# SOC_PWR.net
KiCad netlist of a schematic drawn in Altium Designer
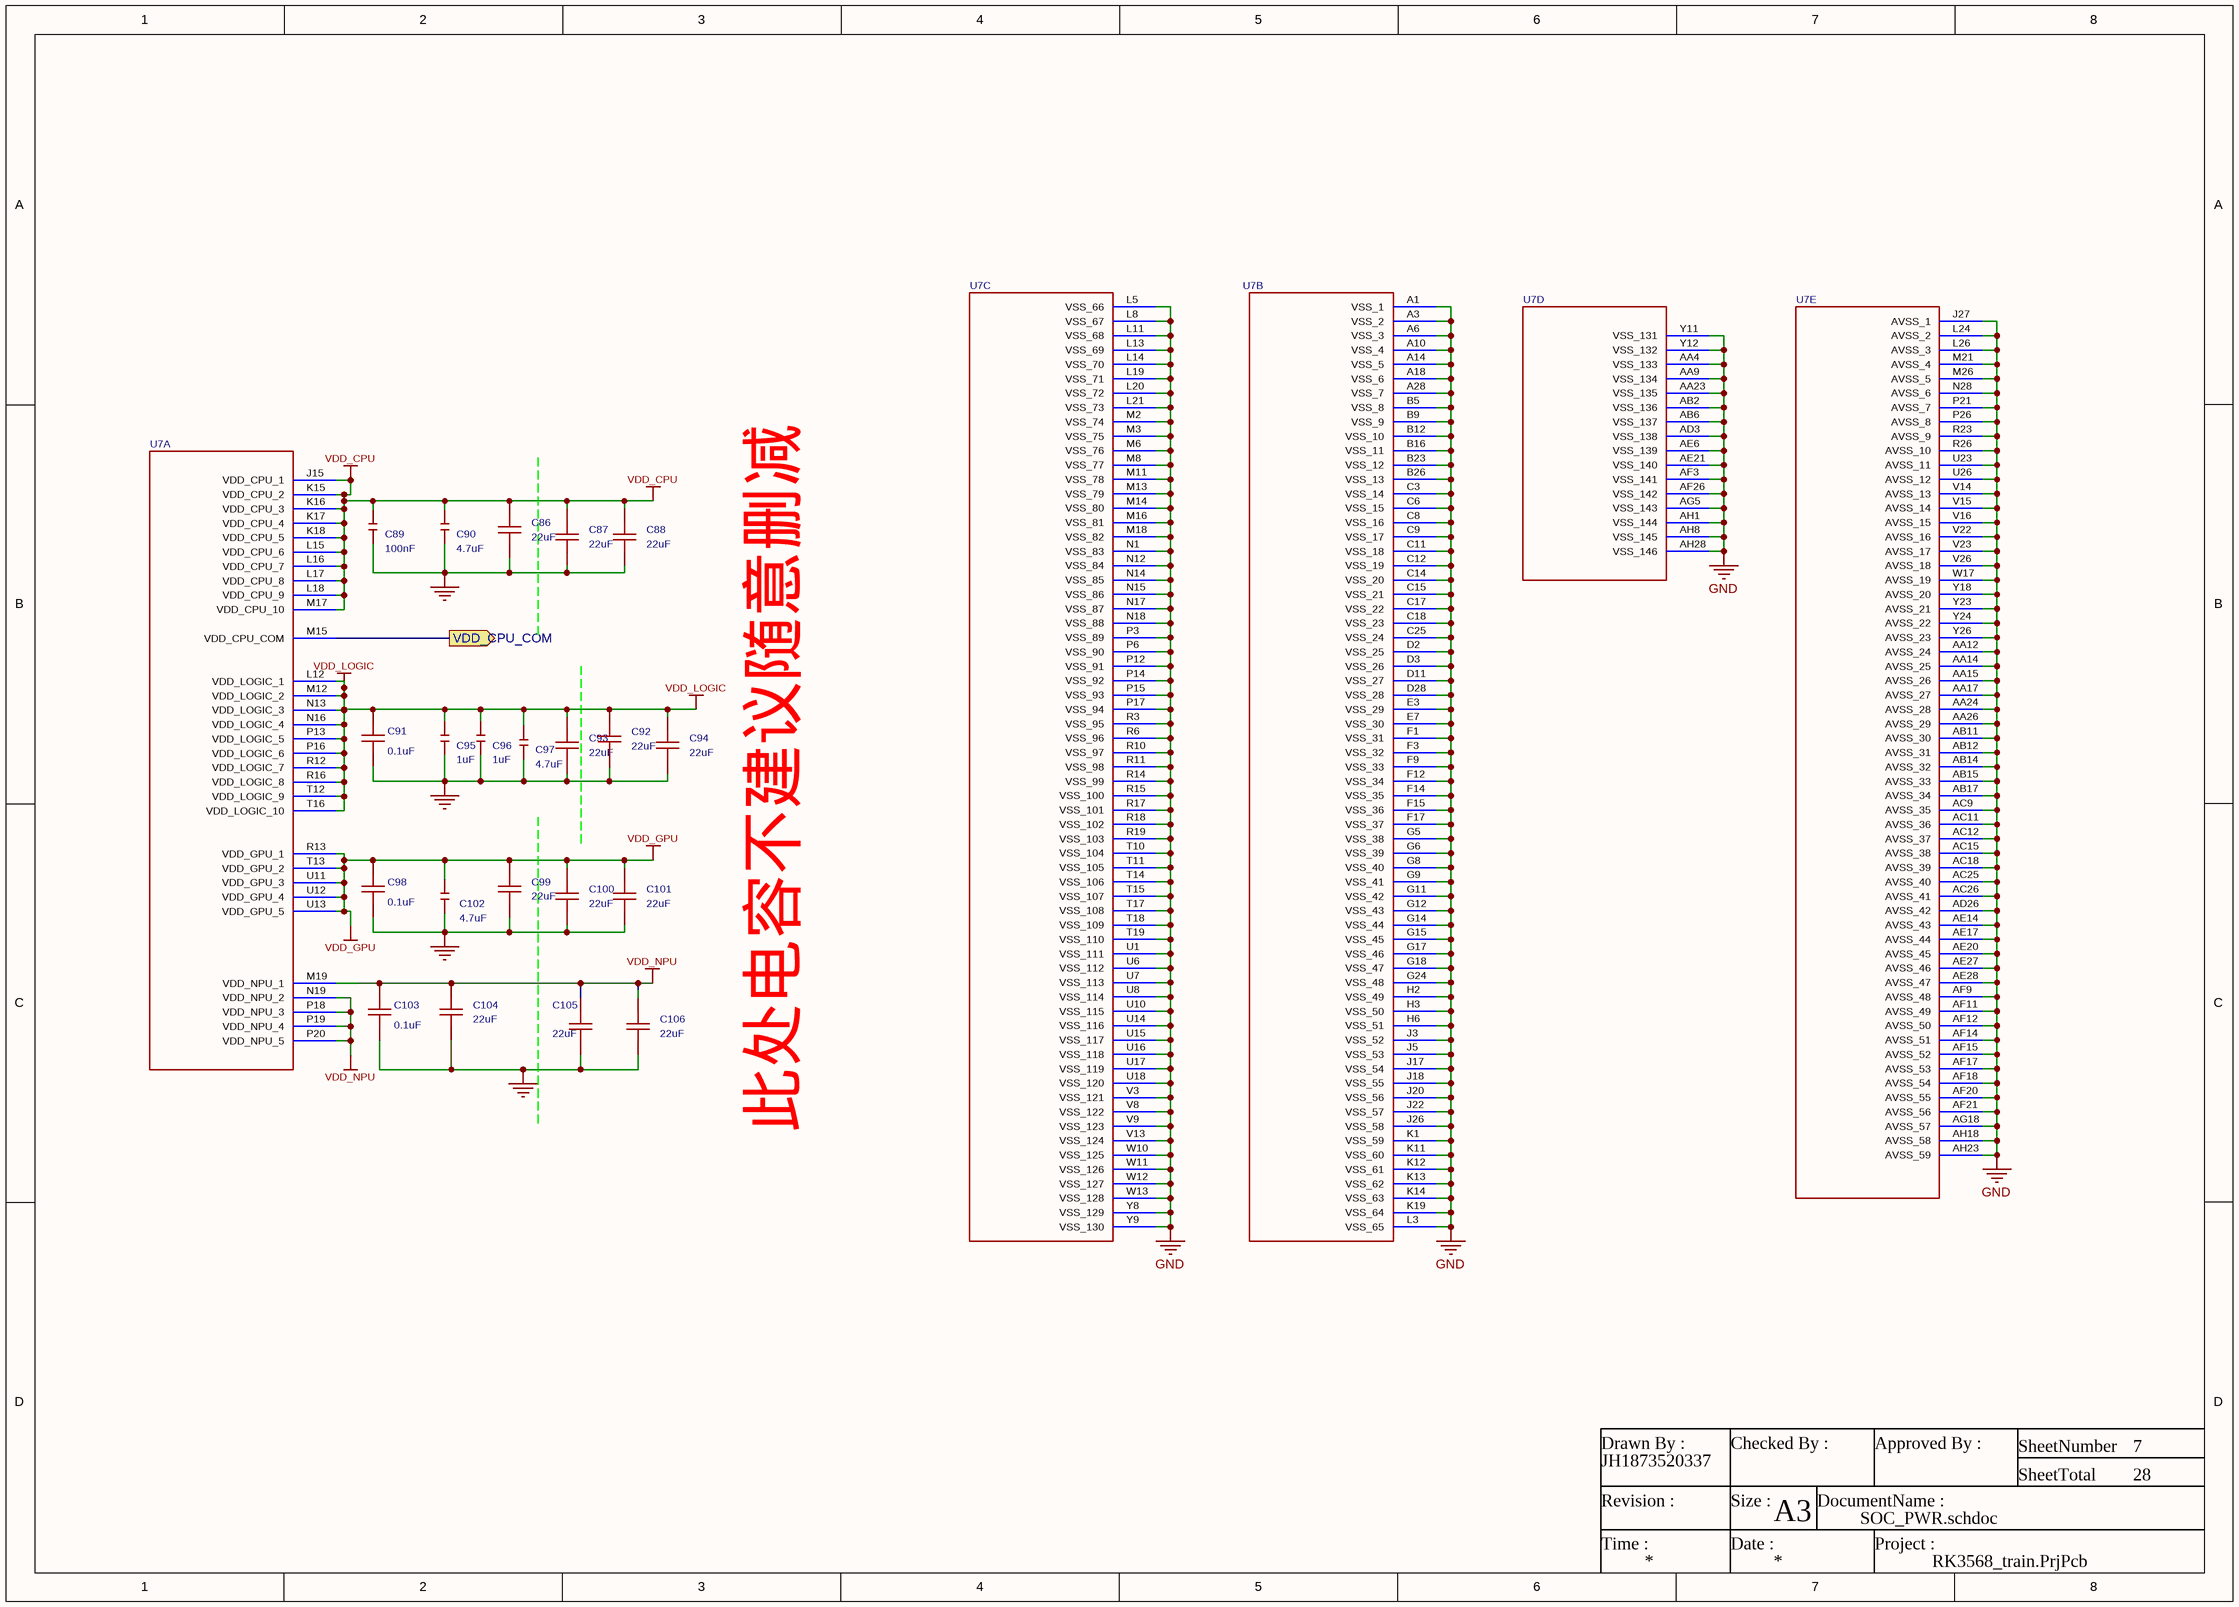
[diagram p0: SOC_PWR.schdoc]

(export (version "E")
  (design (tool "Eeschema 10.0.6"))
  (components
    (comp (ref "C86")
      (value "22uF")
      (footprint "C0603")
      (libsource (lib "altium-import") (part "root_1_CAP_0603_"))
    )
    (comp (ref "C87")
      (value "22uF")
      (footprint "C0603")
      (libsource (lib "altium-import") (part "root_1_CAP_0603_"))
    )
    (comp (ref "C88")
      (value "22uF")
      (footprint "C0603")
      (libsource (lib "altium-import") (part "root_1_CAP_0603_"))
    )
    (comp (ref "C89")
      (value "100nF")
      (footprint "MYC0402")
      (description "C0402电容")
      (libsource (lib "altium-import") (part "root_1_MYC0402_"))
    )
    (comp (ref "C90")
      (value "4.7uF")
      (footprint "MYC0402")
      (description "C0402电容")
      (libsource (lib "altium-import") (part "root_1_MYC0402_"))
    )
    (comp (ref "C91")
      (value "0.1uF")
      (footprint "C0201")
      (description "容值:4.7uF;精度:±20%;额定电压:6.3V;温度系数:X5R;")
      (fields
        (field (name "MANUFACTURER") "muRata(村田)")
        (field (name "MANUFACTURERPART") "GRM035R60J475ME15D")
      )
      (libsource (lib "altium-import") (part "root_0_GRM035R60J475ME15D_"))
    )
    (comp (ref "C92")
      (value "22uF")
      (footprint "C0603")
      (libsource (lib "altium-import") (part "root_1_CAP_0603_"))
    )
    (comp (ref "C93")
      (value "22uF")
      (footprint "C0603")
      (libsource (lib "altium-import") (part "root_1_CAP_0603_"))
    )
    (comp (ref "C94")
      (value "22uF")
      (footprint "C0603")
      (libsource (lib "altium-import") (part "root_1_CAP_0603_"))
    )
    (comp (ref "C95")
      (value "1uF")
      (footprint "MYC0402")
      (description "C0402电容")
      (libsource (lib "altium-import") (part "root_1_MYC0402_"))
    )
    (comp (ref "C96")
      (value "1uF")
      (footprint "MYC0402")
      (description "C0402电容")
      (libsource (lib "altium-import") (part "root_1_MYC0402_"))
    )
    (comp (ref "C97")
      (value "4.7uF")
      (footprint "MYC0402")
      (description "C0402电容")
      (libsource (lib "altium-import") (part "root_1_MYC0402_"))
    )
    (comp (ref "C98")
      (value "0.1uF")
      (footprint "C0201")
      (description "容值:4.7uF;精度:±20%;额定电压:6.3V;温度系数:X5R;")
      (fields
        (field (name "MANUFACTURER") "muRata(村田)")
        (field (name "MANUFACTURERPART") "GRM035R60J475ME15D")
      )
      (libsource (lib "altium-import") (part "root_0_GRM035R60J475ME15D_"))
    )
    (comp (ref "C99")
      (value "22uF")
      (footprint "C0603")
      (libsource (lib "altium-import") (part "root_1_CAP_0603_"))
    )
    (comp (ref "C100")
      (value "22uF")
      (footprint "C0603")
      (libsource (lib "altium-import") (part "root_1_CAP_0603_"))
    )
    (comp (ref "C101")
      (value "22uF")
      (footprint "C0603")
      (libsource (lib "altium-import") (part "root_1_CAP_0603_"))
    )
    (comp (ref "C102")
      (value "4.7uF")
      (footprint "MYC0402")
      (description "C0402电容")
      (libsource (lib "altium-import") (part "root_1_MYC0402_"))
    )
    (comp (ref "C103")
      (value "0.1uF")
      (footprint "C0201")
      (description "容值:4.7uF;精度:±20%;额定电压:6.3V;温度系数:X5R;")
      (fields
        (field (name "MANUFACTURER") "muRata(村田)")
        (field (name "MANUFACTURERPART") "GRM035R60J475ME15D")
      )
      (libsource (lib "altium-import") (part "root_0_GRM035R60J475ME15D_"))
    )
    (comp (ref "C104")
      (value "22uF")
      (footprint "C0603")
      (libsource (lib "altium-import") (part "root_1_CAP_0603_"))
    )
    (comp (ref "C105")
      (value "22uF")
      (footprint "C0603")
      (libsource (lib "altium-import") (part "root_1_CAP_0603_"))
    )
    (comp (ref "C106")
      (value "22uF")
      (footprint "C0603")
      (libsource (lib "altium-import") (part "root_1_CAP_0603_"))
    )
    (comp (ref "U7")
      (value "RK3568")
      (footprint "BGA-636_L19.0-W19.0-P0.65-BL")
      (libsource (lib "altium-import") (part "root_0_RK3568_"))
    )
  )
  (nets
    (net (code "1") (name "/VDD_CPU_COM") (class "Default")
      (node (ref "U7") (pin "M15") (pinfunction "VDD_CPU_COM_M15") (pintype "passive"))
    )
    (net (code "2") (name "GND") (class "Default")
      (node (ref "C100") (pin "1") (pinfunction "1_1") (pintype "passive"))
      (node (ref "C101") (pin "1") (pinfunction "1_1") (pintype "passive"))
      (node (ref "C102") (pin "1") (pinfunction "1_1") (pintype "passive"))
      (node (ref "C103") (pin "1") (pinfunction "1_1") (pintype "passive"))
      (node (ref "C104") (pin "1") (pinfunction "1_1") (pintype "passive"))
      (node (ref "C105") (pin "1") (pinfunction "1_1") (pintype "passive"))
      (node (ref "C106") (pin "1") (pinfunction "1_1") (pintype "passive"))
      (node (ref "C86") (pin "1") (pinfunction "1_1") (pintype "passive"))
      (node (ref "C87") (pin "1") (pinfunction "1_1") (pintype "passive"))
      (node (ref "C88") (pin "1") (pinfunction "1_1") (pintype "passive"))
      (node (ref "C89") (pin "1") (pinfunction "1_1") (pintype "passive"))
      (node (ref "C90") (pin "1") (pinfunction "1_1") (pintype "passive"))
      (node (ref "C91") (pin "1") (pinfunction "1_1") (pintype "passive"))
      (node (ref "C92") (pin "1") (pinfunction "1_1") (pintype "passive"))
      (node (ref "C93") (pin "1") (pinfunction "1_1") (pintype "passive"))
      (node (ref "C94") (pin "1") (pinfunction "1_1") (pintype "passive"))
      (node (ref "C95") (pin "1") (pinfunction "1_1") (pintype "passive"))
      (node (ref "C96") (pin "1") (pinfunction "1_1") (pintype "passive"))
      (node (ref "C97") (pin "1") (pinfunction "1_1") (pintype "passive"))
      (node (ref "C98") (pin "1") (pinfunction "1_1") (pintype "passive"))
      (node (ref "C99") (pin "1") (pinfunction "1_1") (pintype "passive"))
      (node (ref "U7") (pin "A1") (pinfunction "VSS_1_A1") (pintype "passive"))
      (node (ref "U7") (pin "A10") (pinfunction "VSS_4_A10") (pintype "passive"))
      (node (ref "U7") (pin "A14") (pinfunction "VSS_5_A14") (pintype "passive"))
      (node (ref "U7") (pin "A18") (pinfunction "VSS_6_A18") (pintype "passive"))
      (node (ref "U7") (pin "A28") (pinfunction "VSS_7_A28") (pintype "passive"))
      (node (ref "U7") (pin "A3") (pinfunction "VSS_2_A3") (pintype "passive"))
      (node (ref "U7") (pin "A6") (pinfunction "VSS_3_A6") (pintype "passive"))
      (node (ref "U7") (pin "AA12") (pinfunction "AVSS_24_AA12") (pintype "passive"))
      (node (ref "U7") (pin "AA14") (pinfunction "AVSS_25_AA14") (pintype "passive"))
      (node (ref "U7") (pin "AA15") (pinfunction "AVSS_26_AA15") (pintype "passive"))
      (node (ref "U7") (pin "AA17") (pinfunction "AVSS_27_AA17") (pintype "passive"))
      (node (ref "U7") (pin "AA23") (pinfunction "VSS_135_AA23") (pintype "passive"))
      (node (ref "U7") (pin "AA24") (pinfunction "AVSS_28_AA24") (pintype "passive"))
      (node (ref "U7") (pin "AA26") (pinfunction "AVSS_29_AA26") (pintype "passive"))
      (node (ref "U7") (pin "AA4") (pinfunction "VSS_133_AA4") (pintype "passive"))
      (node (ref "U7") (pin "AA9") (pinfunction "VSS_134_AA9") (pintype "passive"))
      (node (ref "U7") (pin "AB11") (pinfunction "AVSS_30_AB11") (pintype "passive"))
      (node (ref "U7") (pin "AB12") (pinfunction "AVSS_31_AB12") (pintype "passive"))
      (node (ref "U7") (pin "AB14") (pinfunction "AVSS_32_AB14") (pintype "passive"))
      (node (ref "U7") (pin "AB15") (pinfunction "AVSS_33_AB15") (pintype "passive"))
      (node (ref "U7") (pin "AB17") (pinfunction "AVSS_34_AB17") (pintype "passive"))
      (node (ref "U7") (pin "AB2") (pinfunction "VSS_136_AB2") (pintype "passive"))
      (node (ref "U7") (pin "AB6") (pinfunction "VSS_137_AB6") (pintype "passive"))
      (node (ref "U7") (pin "AC11") (pinfunction "AVSS_36_AC11") (pintype "passive"))
      (node (ref "U7") (pin "AC12") (pinfunction "AVSS_37_AC12") (pintype "passive"))
      (node (ref "U7") (pin "AC15") (pinfunction "AVSS_38_AC15") (pintype "passive"))
      (node (ref "U7") (pin "AC18") (pinfunction "AVSS_39_AC18") (pintype "passive"))
      (node (ref "U7") (pin "AC25") (pinfunction "AVSS_40_AC25") (pintype "passive"))
      (node (ref "U7") (pin "AC26") (pinfunction "AVSS_41_AC26") (pintype "passive"))
      (node (ref "U7") (pin "AC9") (pinfunction "AVSS_35_AC9") (pintype "passive"))
      (node (ref "U7") (pin "AD26") (pinfunction "AVSS_42_AD26") (pintype "passive"))
      (node (ref "U7") (pin "AD3") (pinfunction "VSS_138_AD3") (pintype "passive"))
      (node (ref "U7") (pin "AE14") (pinfunction "AVSS_43_AE14") (pintype "passive"))
      (node (ref "U7") (pin "AE17") (pinfunction "AVSS_44_AE17") (pintype "passive"))
      (node (ref "U7") (pin "AE20") (pinfunction "AVSS_45_AE20") (pintype "passive"))
      (node (ref "U7") (pin "AE21") (pinfunction "VSS_140_AE21") (pintype "passive"))
      (node (ref "U7") (pin "AE27") (pinfunction "AVSS_46_AE27") (pintype "passive"))
      (node (ref "U7") (pin "AE28") (pinfunction "AVSS_47_AE28") (pintype "passive"))
      (node (ref "U7") (pin "AE6") (pinfunction "VSS_139_AE6") (pintype "passive"))
      (node (ref "U7") (pin "AF11") (pinfunction "AVSS_49_AF11") (pintype "passive"))
      (node (ref "U7") (pin "AF12") (pinfunction "AVSS_50_AF12") (pintype "passive"))
      (node (ref "U7") (pin "AF14") (pinfunction "AVSS_51_AF14") (pintype "passive"))
      (node (ref "U7") (pin "AF15") (pinfunction "AVSS_52_AF15") (pintype "passive"))
      (node (ref "U7") (pin "AF17") (pinfunction "AVSS_53_AF17") (pintype "passive"))
      (node (ref "U7") (pin "AF18") (pinfunction "AVSS_54_AF18") (pintype "passive"))
      (node (ref "U7") (pin "AF20") (pinfunction "AVSS_55_AF20") (pintype "passive"))
      (node (ref "U7") (pin "AF21") (pinfunction "AVSS_56_AF21") (pintype "passive"))
      (node (ref "U7") (pin "AF26") (pinfunction "VSS_142_AF26") (pintype "passive"))
      (node (ref "U7") (pin "AF3") (pinfunction "VSS_141_AF3") (pintype "passive"))
      (node (ref "U7") (pin "AF9") (pinfunction "AVSS_48_AF9") (pintype "passive"))
      (node (ref "U7") (pin "AG18") (pinfunction "AVSS_57_AG18") (pintype "passive"))
      (node (ref "U7") (pin "AG5") (pinfunction "VSS_143_AG5") (pintype "passive"))
      (node (ref "U7") (pin "AH1") (pinfunction "VSS_144_AH1") (pintype "passive"))
      (node (ref "U7") (pin "AH18") (pinfunction "AVSS_58_AH18") (pintype "passive"))
      (node (ref "U7") (pin "AH23") (pinfunction "AVSS_59_AH23") (pintype "passive"))
      (node (ref "U7") (pin "AH28") (pinfunction "VSS_146_AH28") (pintype "passive"))
      (node (ref "U7") (pin "AH8") (pinfunction "VSS_145_AH8") (pintype "passive"))
      (node (ref "U7") (pin "B12") (pinfunction "VSS_10_B12") (pintype "passive"))
      (node (ref "U7") (pin "B16") (pinfunction "VSS_11_B16") (pintype "passive"))
      (node (ref "U7") (pin "B23") (pinfunction "VSS_12_B23") (pintype "passive"))
      (node (ref "U7") (pin "B26") (pinfunction "VSS_13_B26") (pintype "passive"))
      (node (ref "U7") (pin "B5") (pinfunction "VSS_8_B5") (pintype "passive"))
      (node (ref "U7") (pin "B9") (pinfunction "VSS_9_B9") (pintype "passive"))
      (node (ref "U7") (pin "C11") (pinfunction "VSS_18_C11") (pintype "passive"))
      (node (ref "U7") (pin "C12") (pinfunction "VSS_19_C12") (pintype "passive"))
      (node (ref "U7") (pin "C14") (pinfunction "VSS_20_C14") (pintype "passive"))
      (node (ref "U7") (pin "C15") (pinfunction "VSS_21_C15") (pintype "passive"))
      (node (ref "U7") (pin "C17") (pinfunction "VSS_22_C17") (pintype "passive"))
      (node (ref "U7") (pin "C18") (pinfunction "VSS_23_C18") (pintype "passive"))
      (node (ref "U7") (pin "C25") (pinfunction "VSS_24_C25") (pintype "passive"))
      (node (ref "U7") (pin "C3") (pinfunction "VSS_14_C3") (pintype "passive"))
      (node (ref "U7") (pin "C6") (pinfunction "VSS_15_C6") (pintype "passive"))
      (node (ref "U7") (pin "C8") (pinfunction "VSS_16_C8") (pintype "passive"))
      (node (ref "U7") (pin "C9") (pinfunction "VSS_17_C9") (pintype "passive"))
      (node (ref "U7") (pin "D11") (pinfunction "VSS_27_D11") (pintype "passive"))
      (node (ref "U7") (pin "D2") (pinfunction "VSS_25_D2") (pintype "passive"))
      (node (ref "U7") (pin "D28") (pinfunction "VSS_28_D28") (pintype "passive"))
      (node (ref "U7") (pin "D3") (pinfunction "VSS_26_D3") (pintype "passive"))
      (node (ref "U7") (pin "E3") (pinfunction "VSS_29_E3") (pintype "passive"))
      (node (ref "U7") (pin "E7") (pinfunction "VSS_30_E7") (pintype "passive"))
      (node (ref "U7") (pin "F1") (pinfunction "VSS_31_F1") (pintype "passive"))
      (node (ref "U7") (pin "F12") (pinfunction "VSS_34_F12") (pintype "passive"))
      (node (ref "U7") (pin "F14") (pinfunction "VSS_35_F14") (pintype "passive"))
      (node (ref "U7") (pin "F15") (pinfunction "VSS_36_F15") (pintype "passive"))
      (node (ref "U7") (pin "F17") (pinfunction "VSS_37_F17") (pintype "passive"))
      (node (ref "U7") (pin "F3") (pinfunction "VSS_32_F3") (pintype "passive"))
      (node (ref "U7") (pin "F9") (pinfunction "VSS_33_F9") (pintype "passive"))
      (node (ref "U7") (pin "G11") (pinfunction "VSS_42_G11") (pintype "passive"))
      (node (ref "U7") (pin "G12") (pinfunction "VSS_43_G12") (pintype "passive"))
      (node (ref "U7") (pin "G14") (pinfunction "VSS_44_G14") (pintype "passive"))
      (node (ref "U7") (pin "G15") (pinfunction "VSS_45_G15") (pintype "passive"))
      (node (ref "U7") (pin "G17") (pinfunction "VSS_46_G17") (pintype "passive"))
      (node (ref "U7") (pin "G18") (pinfunction "VSS_47_G18") (pintype "passive"))
      (node (ref "U7") (pin "G24") (pinfunction "VSS_48_G24") (pintype "passive"))
      (node (ref "U7") (pin "G5") (pinfunction "VSS_38_G5") (pintype "passive"))
      (node (ref "U7") (pin "G6") (pinfunction "VSS_39_G6") (pintype "passive"))
      (node (ref "U7") (pin "G8") (pinfunction "VSS_40_G8") (pintype "passive"))
      (node (ref "U7") (pin "G9") (pinfunction "VSS_41_G9") (pintype "passive"))
      (node (ref "U7") (pin "H2") (pinfunction "VSS_49_H2") (pintype "passive"))
      (node (ref "U7") (pin "H3") (pinfunction "VSS_50_H3") (pintype "passive"))
      (node (ref "U7") (pin "H6") (pinfunction "VSS_51_H6") (pintype "passive"))
      (node (ref "U7") (pin "J17") (pinfunction "VSS_54_J17") (pintype "passive"))
      (node (ref "U7") (pin "J18") (pinfunction "VSS_55_J18") (pintype "passive"))
      (node (ref "U7") (pin "J20") (pinfunction "VSS_56_J20") (pintype "passive"))
      (node (ref "U7") (pin "J22") (pinfunction "VSS_57_J22") (pintype "passive"))
      (node (ref "U7") (pin "J26") (pinfunction "VSS_58_J26") (pintype "passive"))
      (node (ref "U7") (pin "J27") (pinfunction "AVSS_1_J27") (pintype "passive"))
      (node (ref "U7") (pin "J3") (pinfunction "VSS_52_J3") (pintype "passive"))
      (node (ref "U7") (pin "J5") (pinfunction "VSS_53_J5") (pintype "passive"))
      (node (ref "U7") (pin "K1") (pinfunction "VSS_59_K1") (pintype "passive"))
      (node (ref "U7") (pin "K11") (pinfunction "VSS_60_K11") (pintype "passive"))
      (node (ref "U7") (pin "K12") (pinfunction "VSS_61_K12") (pintype "passive"))
      (node (ref "U7") (pin "K13") (pinfunction "VSS_62_K13") (pintype "passive"))
      (node (ref "U7") (pin "K14") (pinfunction "VSS_63_K14") (pintype "passive"))
      (node (ref "U7") (pin "K19") (pinfunction "VSS_64_K19") (pintype "passive"))
      (node (ref "U7") (pin "L11") (pinfunction "VSS_68_L11") (pintype "passive"))
      (node (ref "U7") (pin "L13") (pinfunction "VSS_69_L13") (pintype "passive"))
      (node (ref "U7") (pin "L14") (pinfunction "VSS_70_L14") (pintype "passive"))
      (node (ref "U7") (pin "L19") (pinfunction "VSS_71_L19") (pintype "passive"))
      (node (ref "U7") (pin "L20") (pinfunction "VSS_72_L20") (pintype "passive"))
      (node (ref "U7") (pin "L21") (pinfunction "VSS_73_L21") (pintype "passive"))
      (node (ref "U7") (pin "L24") (pinfunction "AVSS_2_L24") (pintype "passive"))
      (node (ref "U7") (pin "L26") (pinfunction "AVSS_3_L26") (pintype "passive"))
      (node (ref "U7") (pin "L3") (pinfunction "VSS_65_L3") (pintype "passive"))
      (node (ref "U7") (pin "L5") (pinfunction "VSS_66_L5") (pintype "passive"))
      (node (ref "U7") (pin "L8") (pinfunction "VSS_67_L8") (pintype "passive"))
      (node (ref "U7") (pin "M11") (pinfunction "VSS_78_M11") (pintype "passive"))
      (node (ref "U7") (pin "M13") (pinfunction "VSS_79_M13") (pintype "passive"))
      (node (ref "U7") (pin "M14") (pinfunction "VSS_80_M14") (pintype "passive"))
      (node (ref "U7") (pin "M16") (pinfunction "VSS_81_M16") (pintype "passive"))
      (node (ref "U7") (pin "M18") (pinfunction "VSS_82_M18") (pintype "passive"))
      (node (ref "U7") (pin "M2") (pinfunction "VSS_74_M2") (pintype "passive"))
      (node (ref "U7") (pin "M21") (pinfunction "AVSS_4_M21") (pintype "passive"))
      (node (ref "U7") (pin "M26") (pinfunction "AVSS_5_M26") (pintype "passive"))
      (node (ref "U7") (pin "M3") (pinfunction "VSS_75_M3") (pintype "passive"))
      (node (ref "U7") (pin "M6") (pinfunction "VSS_76_M6") (pintype "passive"))
      (node (ref "U7") (pin "M8") (pinfunction "VSS_77_M8") (pintype "passive"))
      (node (ref "U7") (pin "N1") (pinfunction "VSS_83_N1") (pintype "passive"))
      (node (ref "U7") (pin "N12") (pinfunction "VSS_84_N12") (pintype "passive"))
      (node (ref "U7") (pin "N14") (pinfunction "VSS_85_N14") (pintype "passive"))
      (node (ref "U7") (pin "N15") (pinfunction "VSS_86_N15") (pintype "passive"))
      (node (ref "U7") (pin "N17") (pinfunction "VSS_87_N17") (pintype "passive"))
      (node (ref "U7") (pin "N18") (pinfunction "VSS_88_N18") (pintype "passive"))
      (node (ref "U7") (pin "N28") (pinfunction "AVSS_6_N28") (pintype "passive"))
      (node (ref "U7") (pin "P12") (pinfunction "VSS_91_P12") (pintype "passive"))
      (node (ref "U7") (pin "P14") (pinfunction "VSS_92_P14") (pintype "passive"))
      (node (ref "U7") (pin "P15") (pinfunction "VSS_93_P15") (pintype "passive"))
      (node (ref "U7") (pin "P17") (pinfunction "VSS_94_P17") (pintype "passive"))
      (node (ref "U7") (pin "P21") (pinfunction "AVSS_7_P21") (pintype "passive"))
      (node (ref "U7") (pin "P26") (pinfunction "AVSS_8_P26") (pintype "passive"))
      (node (ref "U7") (pin "P3") (pinfunction "VSS_89_P3") (pintype "passive"))
      (node (ref "U7") (pin "P6") (pinfunction "VSS_90_P6") (pintype "passive"))
      (node (ref "U7") (pin "R10") (pinfunction "VSS_97_R10") (pintype "passive"))
      (node (ref "U7") (pin "R11") (pinfunction "VSS_98_R11") (pintype "passive"))
      (node (ref "U7") (pin "R14") (pinfunction "VSS_99_R14") (pintype "passive"))
      (node (ref "U7") (pin "R15") (pinfunction "VSS_100_R15") (pintype "passive"))
      (node (ref "U7") (pin "R17") (pinfunction "VSS_101_R17") (pintype "passive"))
      (node (ref "U7") (pin "R18") (pinfunction "VSS_102_R18") (pintype "passive"))
      (node (ref "U7") (pin "R19") (pinfunction "VSS_103_R19") (pintype "passive"))
      (node (ref "U7") (pin "R23") (pinfunction "AVSS_9_R23") (pintype "passive"))
      (node (ref "U7") (pin "R26") (pinfunction "AVSS_10_R26") (pintype "passive"))
      (node (ref "U7") (pin "R3") (pinfunction "VSS_95_R3") (pintype "passive"))
      (node (ref "U7") (pin "R6") (pinfunction "VSS_96_R6") (pintype "passive"))
      (node (ref "U7") (pin "T10") (pinfunction "VSS_104_T10") (pintype "passive"))
      (node (ref "U7") (pin "T11") (pinfunction "VSS_105_T11") (pintype "passive"))
      (node (ref "U7") (pin "T14") (pinfunction "VSS_106_T14") (pintype "passive"))
      (node (ref "U7") (pin "T15") (pinfunction "VSS_107_T15") (pintype "passive"))
      (node (ref "U7") (pin "T17") (pinfunction "VSS_108_T17") (pintype "passive"))
      (node (ref "U7") (pin "T18") (pinfunction "VSS_109_T18") (pintype "passive"))
      (node (ref "U7") (pin "T19") (pinfunction "VSS_110_T19") (pintype "passive"))
      (node (ref "U7") (pin "U1") (pinfunction "VSS_111_U1") (pintype "passive"))
      (node (ref "U7") (pin "U10") (pinfunction "VSS_115_U10") (pintype "passive"))
      (node (ref "U7") (pin "U14") (pinfunction "VSS_116_U14") (pintype "passive"))
      (node (ref "U7") (pin "U15") (pinfunction "VSS_117_U15") (pintype "passive"))
      (node (ref "U7") (pin "U16") (pinfunction "VSS_118_U16") (pintype "passive"))
      (node (ref "U7") (pin "U17") (pinfunction "VSS_119_U17") (pintype "passive"))
      (node (ref "U7") (pin "U18") (pinfunction "VSS_120_U18") (pintype "passive"))
      (node (ref "U7") (pin "U23") (pinfunction "AVSS_11_U23") (pintype "passive"))
      (node (ref "U7") (pin "U26") (pinfunction "AVSS_12_U26") (pintype "passive"))
      (node (ref "U7") (pin "U6") (pinfunction "VSS_112_U6") (pintype "passive"))
      (node (ref "U7") (pin "U7") (pinfunction "VSS_113_U7") (pintype "passive"))
      (node (ref "U7") (pin "U8") (pinfunction "VSS_114_U8") (pintype "passive"))
      (node (ref "U7") (pin "V13") (pinfunction "VSS_124_V13") (pintype "passive"))
      (node (ref "U7") (pin "V14") (pinfunction "AVSS_13_V14") (pintype "passive"))
      (node (ref "U7") (pin "V15") (pinfunction "AVSS_14_V15") (pintype "passive"))
      (node (ref "U7") (pin "V16") (pinfunction "AVSS_15_V16") (pintype "passive"))
      (node (ref "U7") (pin "V22") (pinfunction "AVSS_16_V22") (pintype "passive"))
      (node (ref "U7") (pin "V23") (pinfunction "AVSS_17_V23") (pintype "passive"))
      (node (ref "U7") (pin "V26") (pinfunction "AVSS_18_V26") (pintype "passive"))
      (node (ref "U7") (pin "V3") (pinfunction "VSS_121_V3") (pintype "passive"))
      (node (ref "U7") (pin "V8") (pinfunction "VSS_122_V8") (pintype "passive"))
      (node (ref "U7") (pin "V9") (pinfunction "VSS_123_V9") (pintype "passive"))
      (node (ref "U7") (pin "W10") (pinfunction "VSS_125_W10") (pintype "passive"))
      (node (ref "U7") (pin "W11") (pinfunction "VSS_126_W11") (pintype "passive"))
      (node (ref "U7") (pin "W12") (pinfunction "VSS_127_W12") (pintype "passive"))
      (node (ref "U7") (pin "W13") (pinfunction "VSS_128_W13") (pintype "passive"))
      (node (ref "U7") (pin "W17") (pinfunction "AVSS_19_W17") (pintype "passive"))
      (node (ref "U7") (pin "Y11") (pinfunction "VSS_131_Y11") (pintype "passive"))
      (node (ref "U7") (pin "Y12") (pinfunction "VSS_132_Y12") (pintype "passive"))
      (node (ref "U7") (pin "Y18") (pinfunction "AVSS_20_Y18") (pintype "passive"))
      (node (ref "U7") (pin "Y23") (pinfunction "AVSS_21_Y23") (pintype "passive"))
      (node (ref "U7") (pin "Y24") (pinfunction "AVSS_22_Y24") (pintype "passive"))
      (node (ref "U7") (pin "Y26") (pinfunction "AVSS_23_Y26") (pintype "passive"))
      (node (ref "U7") (pin "Y8") (pinfunction "VSS_129_Y8") (pintype "passive"))
      (node (ref "U7") (pin "Y9") (pinfunction "VSS_130_Y9") (pintype "passive"))
    )
    (net (code "3") (name "VDD_CPU") (class "Default")
      (node (ref "C86") (pin "2") (pinfunction "2_2") (pintype "passive"))
      (node (ref "C87") (pin "2") (pinfunction "2_2") (pintype "passive"))
      (node (ref "C88") (pin "2") (pinfunction "2_2") (pintype "passive"))
      (node (ref "C89") (pin "2") (pinfunction "2_2") (pintype "passive"))
      (node (ref "C90") (pin "2") (pinfunction "2_2") (pintype "passive"))
      (node (ref "U7") (pin "J15") (pinfunction "VDD_CPU_1_J15") (pintype "passive"))
      (node (ref "U7") (pin "K15") (pinfunction "VDD_CPU_2_K15") (pintype "passive"))
      (node (ref "U7") (pin "K16") (pinfunction "VDD_CPU_3_K16") (pintype "passive"))
      (node (ref "U7") (pin "K17") (pinfunction "VDD_CPU_4_K17") (pintype "passive"))
      (node (ref "U7") (pin "K18") (pinfunction "VDD_CPU_5_K18") (pintype "passive"))
      (node (ref "U7") (pin "L15") (pinfunction "VDD_CPU_6_L15") (pintype "passive"))
      (node (ref "U7") (pin "L16") (pinfunction "VDD_CPU_7_L16") (pintype "passive"))
      (node (ref "U7") (pin "L17") (pinfunction "VDD_CPU_8_L17") (pintype "passive"))
      (node (ref "U7") (pin "L18") (pinfunction "VDD_CPU_9_L18") (pintype "passive"))
      (node (ref "U7") (pin "M17") (pinfunction "VDD_CPU_10_M17") (pintype "passive"))
    )
    (net (code "4") (name "VDD_GPU") (class "Default")
      (node (ref "C100") (pin "2") (pinfunction "2_2") (pintype "passive"))
      (node (ref "C101") (pin "2") (pinfunction "2_2") (pintype "passive"))
      (node (ref "C102") (pin "2") (pinfunction "2_2") (pintype "passive"))
      (node (ref "C98") (pin "2") (pinfunction "2_2") (pintype "passive"))
      (node (ref "C99") (pin "2") (pinfunction "2_2") (pintype "passive"))
      (node (ref "U7") (pin "R13") (pinfunction "VDD_GPU_1_R13") (pintype "passive"))
      (node (ref "U7") (pin "T13") (pinfunction "VDD_GPU_2_T13") (pintype "passive"))
      (node (ref "U7") (pin "U11") (pinfunction "VDD_GPU_3_U11") (pintype "passive"))
      (node (ref "U7") (pin "U12") (pinfunction "VDD_GPU_4_U12") (pintype "passive"))
      (node (ref "U7") (pin "U13") (pinfunction "VDD_GPU_5_U13") (pintype "passive"))
    )
    (net (code "5") (name "VDD_LOGIC") (class "Default")
      (node (ref "C91") (pin "2") (pinfunction "2_2") (pintype "passive"))
      (node (ref "C92") (pin "2") (pinfunction "2_2") (pintype "passive"))
      (node (ref "C93") (pin "2") (pinfunction "2_2") (pintype "passive"))
      (node (ref "C94") (pin "2") (pinfunction "2_2") (pintype "passive"))
      (node (ref "C95") (pin "2") (pinfunction "2_2") (pintype "passive"))
      (node (ref "C96") (pin "2") (pinfunction "2_2") (pintype "passive"))
      (node (ref "C97") (pin "2") (pinfunction "2_2") (pintype "passive"))
      (node (ref "U7") (pin "L12") (pinfunction "VDD_LOGIC_1_L12") (pintype "passive"))
      (node (ref "U7") (pin "M12") (pinfunction "VDD_LOGIC_2_M12") (pintype "passive"))
      (node (ref "U7") (pin "N13") (pinfunction "VDD_LOGIC_3_N13") (pintype "passive"))
      (node (ref "U7") (pin "N16") (pinfunction "VDD_LOGIC_4_N16") (pintype "passive"))
      (node (ref "U7") (pin "P13") (pinfunction "VDD_LOGIC_5_P13") (pintype "passive"))
      (node (ref "U7") (pin "P16") (pinfunction "VDD_LOGIC_6_P16") (pintype "passive"))
      (node (ref "U7") (pin "R12") (pinfunction "VDD_LOGIC_7_R12") (pintype "passive"))
      (node (ref "U7") (pin "R16") (pinfunction "VDD_LOGIC_8_R16") (pintype "passive"))
      (node (ref "U7") (pin "T12") (pinfunction "VDD_LOGIC_9_T12") (pintype "passive"))
      (node (ref "U7") (pin "T16") (pinfunction "VDD_LOGIC_10_T16") (pintype "passive"))
    )
    (net (code "6") (name "VDD_NPU") (class "Default")
      (node (ref "C103") (pin "2") (pinfunction "2_2") (pintype "passive"))
      (node (ref "C104") (pin "2") (pinfunction "2_2") (pintype "passive"))
      (node (ref "C105") (pin "2") (pinfunction "2_2") (pintype "passive"))
      (node (ref "C106") (pin "2") (pinfunction "2_2") (pintype "passive"))
      (node (ref "U7") (pin "M19") (pinfunction "VDD_NPU_1_M19") (pintype "passive"))
      (node (ref "U7") (pin "N19") (pinfunction "VDD_NPU_2_N19") (pintype "passive"))
      (node (ref "U7") (pin "P18") (pinfunction "VDD_NPU_3_P18") (pintype "passive"))
      (node (ref "U7") (pin "P19") (pinfunction "VDD_NPU_4_P19") (pintype "passive"))
      (node (ref "U7") (pin "P20") (pinfunction "VDD_NPU_5_P20") (pintype "passive"))
    )
  )
)
